# RFM95_LoRa_Shieldv0_2.net
KiCad netlist of a schematic drawn in EAGLE
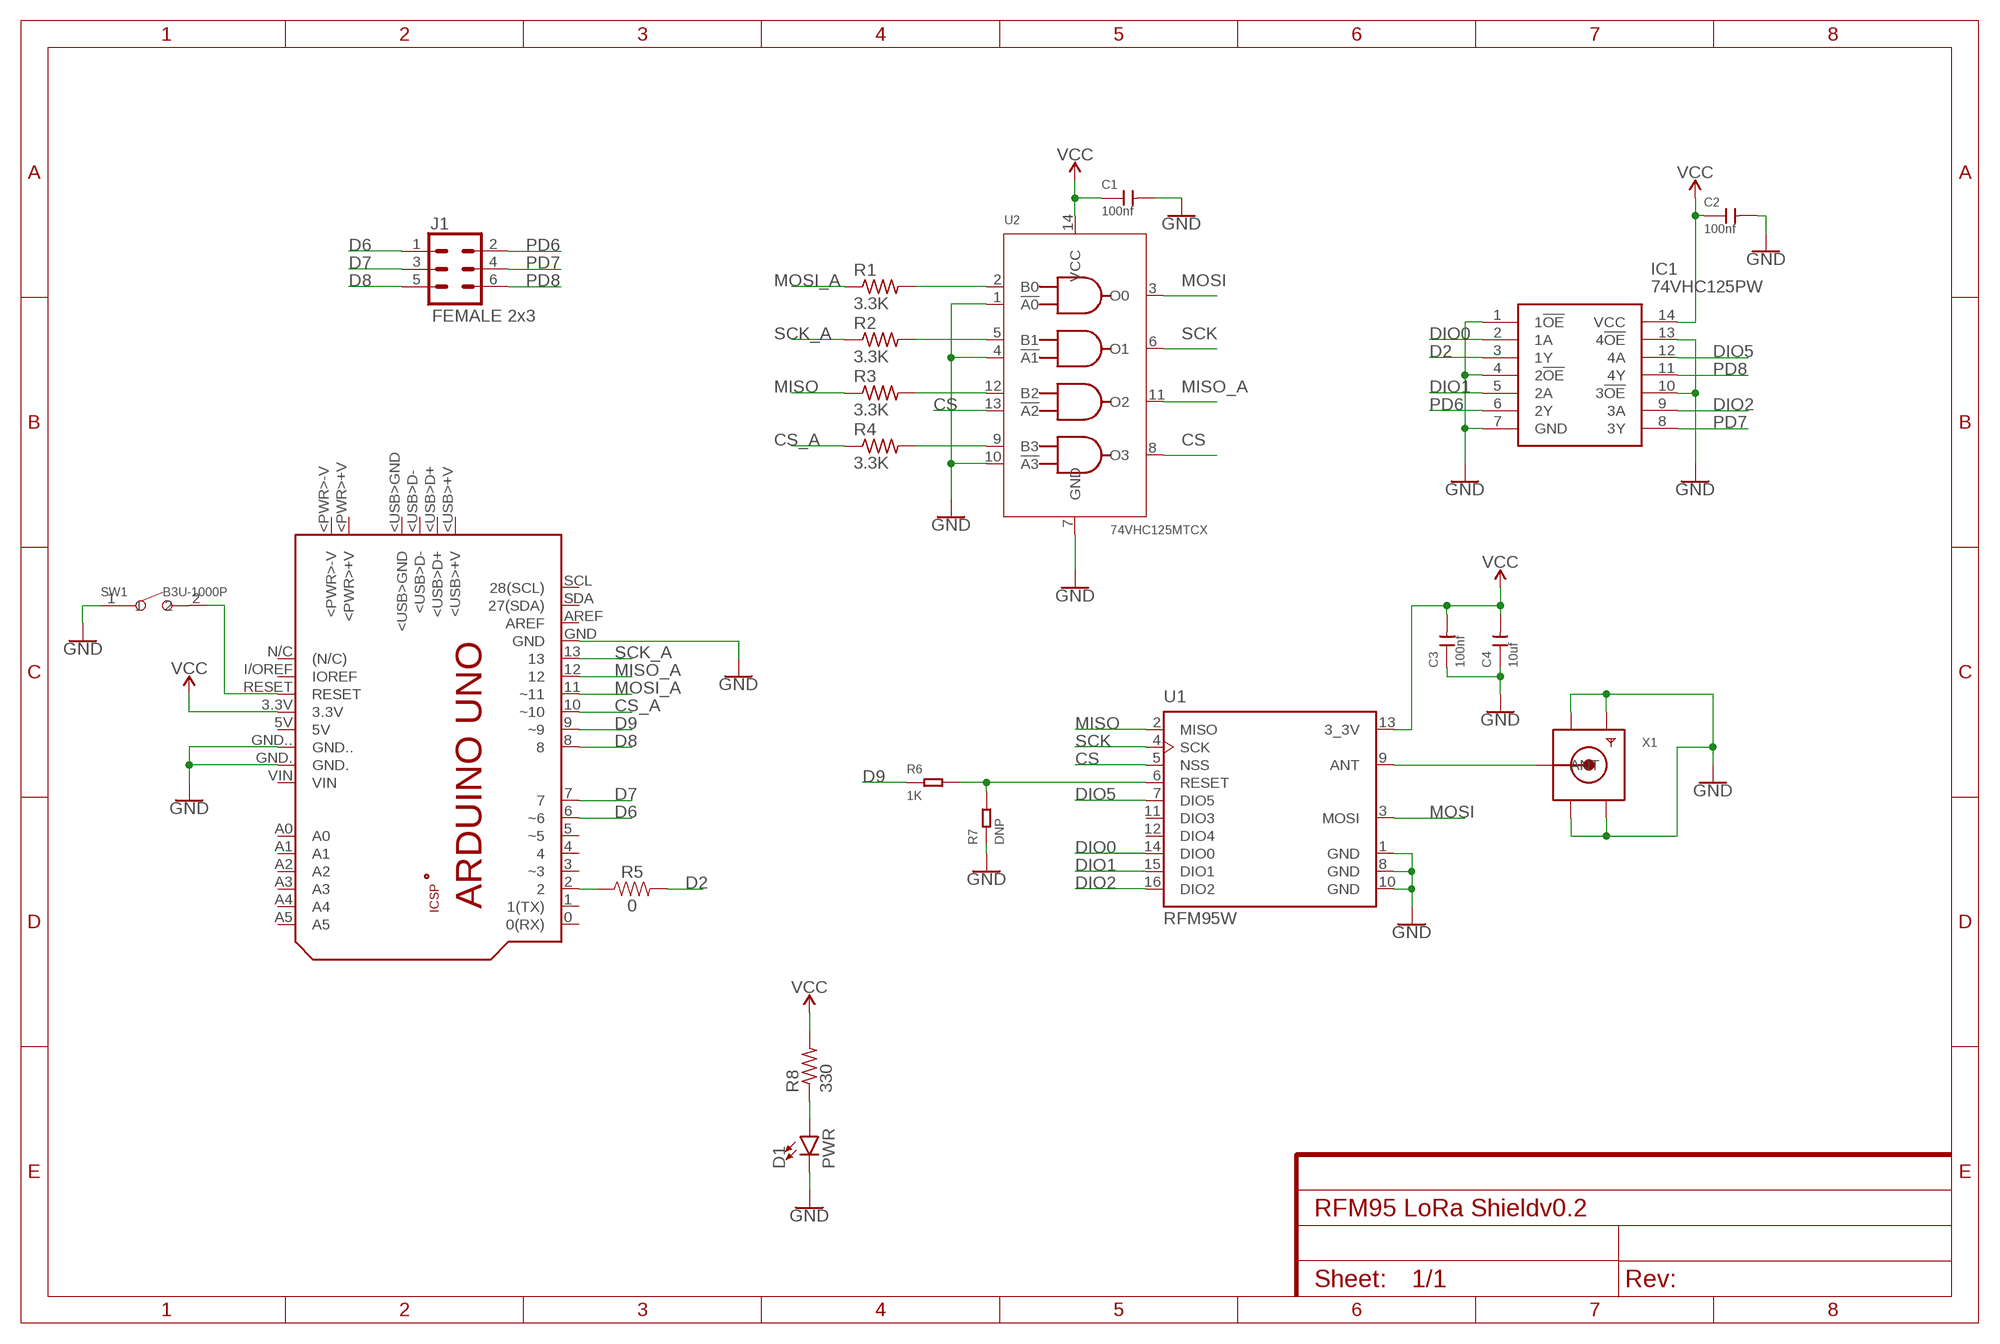
[diagram p0: schematic, sheet 1]

(export (version "E")
  (design (tool "Eeschema 10.0.6"))
  (components
    (comp (ref "C1")
      (value "100nf")
      (footprint "eagle-import:C0805")
      (fields (field (name "MPN") "CC0805KRX7R9BB104"))
      (libsource (lib "eagle-import") (part "CERAMIC-100NF-50V-10%-X7R(0805)"))
    )
    (comp (ref "C2")
      (value "100nf")
      (footprint "eagle-import:C0805")
      (fields (field (name "MPN") "CC0805KRX7R9BB104"))
      (libsource (lib "eagle-import") (part "CERAMIC-100NF-50V-10%-X7R(0805)"))
    )
    (comp (ref "C3")
      (value "100nf")
      (footprint "eagle-import:C0805")
      (fields (field (name "MPN") "CC0805KRX7R9BB104"))
      (libsource (lib "eagle-import") (part "CERAMIC-100NF-50V-10%-X7R(0805)"))
    )
    (comp (ref "C4")
      (value "10uf")
      (footprint "eagle-import:C0805")
      (fields (field (name "MPN") "CC0805KKX5R8BB106"))
      (libsource (lib "eagle-import") (part "CERAMIC-10UF-25V-10%-X5R(0805)"))
    )
    (comp (ref "D1")
      (value "PWR")
      (footprint "eagle-import:LED-1206")
      (libsource (lib "eagle-import") (part "LED-GREEN1206"))
    )
    (comp (ref "IC1")
      (value "74VHC125PW")
      (footprint "eagle-import:SOP65P640X110-14N")
      (fields (field (name "MANUFACTURER_PART_NUMBER") "74VHC125PW,118"))
      (libsource (lib "eagle-import") (part "74VHC125PW,118"))
    )
    (comp (ref "J1")
      (value "FEMALE 2x3")
      (footprint "eagle-import:2X3")
      (libsource (lib "eagle-import") (part "CONN_03X2FEMALE"))
    )
    (comp (ref "PCB1")
      (value "Arduino Uno")
      (footprint "eagle-import:ARDUINO_UNO")
      (libsource (lib "eagle-import") (part "ARDUINO_UNO"))
    )
    (comp (ref "R1")
      (value "3.3K")
      (footprint "eagle-import:M0805")
      (libsource (lib "eagle-import") (part "R-US_M0805"))
    )
    (comp (ref "R2")
      (value "3.3K")
      (footprint "eagle-import:M0805")
      (libsource (lib "eagle-import") (part "R-US_M0805"))
    )
    (comp (ref "R3")
      (value "3.3K")
      (footprint "eagle-import:M0805")
      (libsource (lib "eagle-import") (part "R-US_M0805"))
    )
    (comp (ref "R4")
      (value "3.3K")
      (footprint "eagle-import:M0805")
      (libsource (lib "eagle-import") (part "R-US_M0805"))
    )
    (comp (ref "R5")
      (value "0")
      (footprint "eagle-import:0603")
      (libsource (lib "eagle-import") (part "0OHM-0603-1/10W-5%"))
    )
    (comp (ref "R6")
      (value "1K")
      (footprint "eagle-import:R0805")
      (fields (field (name "MPN") "RC0805JR-071KL"))
      (libsource (lib "eagle-import") (part "SMD-RES-1K-5%-1/8W(0805)"))
    )
    (comp (ref "R7")
      (value "DNP")
      (footprint "eagle-import:R0805")
      (fields (field (name "MPN") "RC0805JR-071KL"))
      (libsource (lib "eagle-import") (part "SMD-RES-1K-5%-1/8W(0805)"))
    )
    (comp (ref "R8")
      (value "330")
      (footprint "eagle-import:M0805")
      (libsource (lib "eagle-import") (part "R-US_M0805"))
    )
    (comp (ref "SW1")
      (value "B3U-1000P")
      (footprint "eagle-import:SW2-2.6-3.0X2.5X1.2+0.4MM")
      (fields (field (name "MPN") "B3U-1000P-2P-SMD"))
      (libsource (lib "eagle-import") (part "SMD-BUTTON(2P-3.0X2.5X1.2+0.4MM)-B3U-1000P-2P-SMD"))
    )
    (comp (ref "U1")
      (value "RFM95W")
      (footprint "eagle-import:XCVR_RFM95W-868S2")
      (fields (field (name "MF") "RF") (field (name "MP") "RFM95W-868S2"))
      (libsource (lib "eagle-import") (part "RFM95W-868S2"))
    )
    (comp (ref "U2")
      (value "74VHC125MTCX")
      (footprint "eagle-import:TSSOP14-0.65-5X4.4MM")
      (libsource (lib "eagle-import") (part "LOGIC-74VHC125MTCX(TSSOP14)"))
    )
    (comp (ref "X1")
      (value "SMACONNECTOR")
      (footprint "eagle-import:SMA90_DIP")
      (libsource (lib "eagle-import") (part "SMACONNECTOR"))
    )
  )
  (nets
    (net (code "1") (name "/CS") (class "Default")
      (node (ref "U1") (pin "5") (pinfunction "NSS_5") (pintype "input"))
      (node (ref "U2") (pin "13") (pinfunction "~{A2}_13") (pintype "input"))
      (node (ref "U2") (pin "8") (pinfunction "O3_8") (pintype "bidirectional"))
    )
    (net (code "2") (name "/CS_A") (class "Default")
      (node (ref "PCB1") (pin "10") (pinfunction "~{10}_10") (pintype "bidirectional"))
      (node (ref "R4") (pin "1") (pinfunction "1_1") (pintype "passive"))
    )
    (net (code "3") (name "/D2") (class "Default")
      (node (ref "IC1") (pin "3") (pinfunction "1Y_3") (pintype "bidirectional"))
      (node (ref "R5") (pin "2") (pinfunction "2_2") (pintype "passive"))
    )
    (net (code "4") (name "/D6") (class "Default")
      (node (ref "J1") (pin "1") (pinfunction "1_1") (pintype "bidirectional"))
      (node (ref "PCB1") (pin "6") (pinfunction "~{6}_6") (pintype "bidirectional"))
    )
    (net (code "5") (name "/D7") (class "Default")
      (node (ref "J1") (pin "3") (pinfunction "3_3") (pintype "bidirectional"))
      (node (ref "PCB1") (pin "7") (pinfunction "7_7") (pintype "bidirectional"))
    )
    (net (code "6") (name "/D8") (class "Default")
      (node (ref "J1") (pin "5") (pinfunction "5_5") (pintype "bidirectional"))
      (node (ref "PCB1") (pin "8") (pinfunction "8_8") (pintype "bidirectional"))
    )
    (net (code "7") (name "/D9") (class "Default")
      (node (ref "PCB1") (pin "9") (pinfunction "~{9}_9") (pintype "bidirectional"))
      (node (ref "R6") (pin "1") (pinfunction "1_1") (pintype "passive"))
    )
    (net (code "8") (name "/DIO0") (class "Default")
      (node (ref "IC1") (pin "2") (pinfunction "1A_2") (pintype "bidirectional"))
      (node (ref "U1") (pin "14") (pinfunction "DIO0_14") (pintype "bidirectional"))
    )
    (net (code "9") (name "/DIO1") (class "Default")
      (node (ref "IC1") (pin "5") (pinfunction "2A_5") (pintype "bidirectional"))
      (node (ref "U1") (pin "15") (pinfunction "DIO1_15") (pintype "bidirectional"))
    )
    (net (code "10") (name "/DIO2") (class "Default")
      (node (ref "IC1") (pin "9") (pinfunction "3A_9") (pintype "bidirectional"))
      (node (ref "U1") (pin "16") (pinfunction "DIO2_16") (pintype "bidirectional"))
    )
    (net (code "11") (name "/DIO5") (class "Default")
      (node (ref "IC1") (pin "12") (pinfunction "4A_12") (pintype "bidirectional"))
      (node (ref "U1") (pin "7") (pinfunction "DIO5_7") (pintype "bidirectional"))
    )
    (net (code "12") (name "/MISO") (class "Default")
      (node (ref "R3") (pin "1") (pinfunction "1_1") (pintype "passive"))
      (node (ref "U1") (pin "2") (pinfunction "MISO_2") (pintype "input"))
    )
    (net (code "13") (name "/MISO_A") (class "Default")
      (node (ref "PCB1") (pin "12") (pinfunction "12_12") (pintype "bidirectional"))
      (node (ref "U2") (pin "11") (pinfunction "O2_11") (pintype "bidirectional"))
    )
    (net (code "14") (name "/MOSI") (class "Default")
      (node (ref "U1") (pin "3") (pinfunction "MOSI_3") (pintype "output"))
      (node (ref "U2") (pin "3") (pinfunction "O0_3") (pintype "bidirectional"))
    )
    (net (code "15") (name "/MOSI_A") (class "Default")
      (node (ref "PCB1") (pin "11") (pinfunction "~{11}_11") (pintype "bidirectional"))
      (node (ref "R1") (pin "1") (pinfunction "1_1") (pintype "passive"))
    )
    (net (code "16") (name "/PD6") (class "Default")
      (node (ref "IC1") (pin "6") (pinfunction "2Y_6") (pintype "bidirectional"))
      (node (ref "J1") (pin "2") (pinfunction "2_2") (pintype "bidirectional"))
    )
    (net (code "17") (name "/PD7") (class "Default")
      (node (ref "IC1") (pin "8") (pinfunction "3Y_8") (pintype "bidirectional"))
      (node (ref "J1") (pin "4") (pinfunction "4_4") (pintype "bidirectional"))
    )
    (net (code "18") (name "/PD8") (class "Default")
      (node (ref "IC1") (pin "11") (pinfunction "4Y_11") (pintype "bidirectional"))
      (node (ref "J1") (pin "6") (pinfunction "6_6") (pintype "bidirectional"))
    )
    (net (code "19") (name "/SCK") (class "Default")
      (node (ref "U1") (pin "4") (pinfunction "SCK_4") (pintype "input"))
      (node (ref "U2") (pin "6") (pinfunction "O1_6") (pintype "bidirectional"))
    )
    (net (code "20") (name "/SCK_A") (class "Default")
      (node (ref "PCB1") (pin "13") (pinfunction "13_13") (pintype "bidirectional"))
      (node (ref "R2") (pin "1") (pinfunction "1_1") (pintype "passive"))
    )
    (net (code "21") (name "GND") (class "Default")
      (node (ref "C1") (pin "2") (pinfunction "2_2") (pintype "passive"))
      (node (ref "C2") (pin "2") (pinfunction "2_2") (pintype "passive"))
      (node (ref "C3") (pin "1") (pinfunction "1_1") (pintype "passive"))
      (node (ref "C4") (pin "1") (pinfunction "1_1") (pintype "passive"))
      (node (ref "D1") (pin "C") (pinfunction "C_C") (pintype "passive"))
      (node (ref "IC1") (pin "1") (pinfunction "1~{OE}_1") (pintype "bidirectional"))
      (node (ref "IC1") (pin "10") (pinfunction "3~{OE}_10") (pintype "bidirectional"))
      (node (ref "IC1") (pin "13") (pinfunction "4~{OE}_13") (pintype "bidirectional"))
      (node (ref "IC1") (pin "4") (pinfunction "2~{OE}_4") (pintype "bidirectional"))
      (node (ref "IC1") (pin "7") (pinfunction "GND_7") (pintype "bidirectional"))
      (node (ref "PCB1") (pin "GND") (pinfunction "GND_GND") (pintype "bidirectional"))
      (node (ref "PCB1") (pin "GND.") (pinfunction "GND._GND.") (pintype "bidirectional"))
      (node (ref "PCB1") (pin "GND..") (pinfunction "GND.._GND..") (pintype "bidirectional"))
      (node (ref "R7") (pin "1") (pinfunction "1_1") (pintype "passive"))
      (node (ref "SW1") (pin "1") (pinfunction "1_1") (pintype "bidirectional"))
      (node (ref "U1") (pin "1") (pinfunction "GND_1") (pintype "power_in"))
      (node (ref "U1") (pin "10") (pinfunction "GND_10") (pintype "power_in"))
      (node (ref "U1") (pin "8") (pinfunction "GND_8") (pintype "power_in"))
      (node (ref "U2") (pin "1") (pinfunction "~{A0}_1") (pintype "power_in"))
      (node (ref "U2") (pin "10") (pinfunction "~{A3}_10") (pintype "bidirectional"))
      (node (ref "U2") (pin "4") (pinfunction "~{A1}_4") (pintype "power_in"))
      (node (ref "U2") (pin "7") (pinfunction "GND_7") (pintype "power_in"))
      (node (ref "X1") (pin "GND1") (pinfunction "GND1_GND1") (pintype "power_in"))
      (node (ref "X1") (pin "GND2") (pinfunction "GND2_GND2") (pintype "power_in"))
      (node (ref "X1") (pin "GND3") (pinfunction "GND3_GND3") (pintype "power_in"))
      (node (ref "X1") (pin "GND4") (pinfunction "GND4_GND4") (pintype "power_in"))
    )
    (net (code "22") (name "Net-(D1-PadA)") (class "Default")
      (node (ref "D1") (pin "A") (pinfunction "A_A") (pintype "passive"))
      (node (ref "R8") (pin "1") (pinfunction "1_1") (pintype "passive"))
    )
    (net (code "23") (name "Net-(PCB1-Pad2)") (class "Default")
      (node (ref "PCB1") (pin "2") (pinfunction "2_2") (pintype "bidirectional"))
      (node (ref "R5") (pin "1") (pinfunction "1_1") (pintype "passive"))
    )
    (net (code "24") (name "Net-(PCB1-PadRESET)") (class "Default")
      (node (ref "PCB1") (pin "RESET") (pinfunction "RESET_RESET") (pintype "bidirectional"))
      (node (ref "SW1") (pin "2") (pinfunction "2_2") (pintype "bidirectional"))
    )
    (net (code "25") (name "Net-(U1-ANT)") (class "Default")
      (node (ref "U1") (pin "9") (pinfunction "ANT_9") (pintype "passive"))
      (node (ref "X1") (pin "ANTENNA") (pinfunction "ANT_ANTENNA") (pintype "bidirectional"))
    )
    (net (code "26") (name "Net-(U1-RESET)") (class "Default")
      (node (ref "R6") (pin "2") (pinfunction "2_2") (pintype "passive"))
      (node (ref "R7") (pin "2") (pinfunction "2_2") (pintype "passive"))
      (node (ref "U1") (pin "6") (pinfunction "RESET_6") (pintype "bidirectional"))
    )
    (net (code "27") (name "Net-(U2-B0)") (class "Default")
      (node (ref "R1") (pin "2") (pinfunction "2_2") (pintype "passive"))
      (node (ref "U2") (pin "2") (pinfunction "B0_2") (pintype "bidirectional"))
    )
    (net (code "28") (name "Net-(U2-B1)") (class "Default")
      (node (ref "R2") (pin "2") (pinfunction "2_2") (pintype "passive"))
      (node (ref "U2") (pin "5") (pinfunction "B1_5") (pintype "bidirectional"))
    )
    (net (code "29") (name "Net-(U2-B2)") (class "Default")
      (node (ref "R3") (pin "2") (pinfunction "2_2") (pintype "passive"))
      (node (ref "U2") (pin "12") (pinfunction "B2_12") (pintype "bidirectional"))
    )
    (net (code "30") (name "Net-(U2-B3)") (class "Default")
      (node (ref "R4") (pin "2") (pinfunction "2_2") (pintype "passive"))
      (node (ref "U2") (pin "9") (pinfunction "B3_9") (pintype "bidirectional"))
    )
    (net (code "31") (name "VCC") (class "Default")
      (node (ref "C1") (pin "1") (pinfunction "1_1") (pintype "passive"))
      (node (ref "C2") (pin "1") (pinfunction "1_1") (pintype "passive"))
      (node (ref "C3") (pin "2") (pinfunction "2_2") (pintype "passive"))
      (node (ref "C4") (pin "2") (pinfunction "2_2") (pintype "passive"))
      (node (ref "IC1") (pin "14") (pinfunction "VCC_14") (pintype "bidirectional"))
      (node (ref "PCB1") (pin "3.3V") (pinfunction "3.3V_3.3V") (pintype "bidirectional"))
      (node (ref "R8") (pin "2") (pinfunction "2_2") (pintype "passive"))
      (node (ref "U1") (pin "13") (pinfunction "3_3V_13") (pintype "power_in"))
      (node (ref "U2") (pin "14") (pinfunction "VCC_14") (pintype "power_in"))
    )
    (net (code "32") (name "unconnected-(PCB1-(N{slash}C)-PadN{slash}C)") (class "Default")
      (node (ref "PCB1") (pin "N/C") (pinfunction "(N/C)_N/C") (pintype "bidirectional"))
    )
    (net (code "33") (name "unconnected-(PCB1-0(RX)-Pad0)") (class "Default")
      (node (ref "PCB1") (pin "0") (pinfunction "0(RX)_0") (pintype "bidirectional"))
    )
    (net (code "34") (name "unconnected-(PCB1-1(TX)-Pad1)") (class "Default")
      (node (ref "PCB1") (pin "1") (pinfunction "1(TX)_1") (pintype "bidirectional"))
    )
    (net (code "35") (name "unconnected-(PCB1-27(SDA)-PadSDA)") (class "Default")
      (node (ref "PCB1") (pin "SDA") (pinfunction "27(SDA)_SDA") (pintype "bidirectional"))
    )
    (net (code "36") (name "unconnected-(PCB1-28(SCL)-PadSCL)") (class "Default")
      (node (ref "PCB1") (pin "SCL") (pinfunction "28(SCL)_SCL") (pintype "bidirectional"))
    )
    (net (code "37") (name "unconnected-(PCB1-IOREF-PadI{slash}OREF)") (class "Default")
      (node (ref "PCB1") (pin "I/OREF") (pinfunction "IOREF_I/OREF") (pintype "bidirectional"))
    )
    (net (code "38") (name "unconnected-(PCB1-Pad+5V)") (class "Default")
      (node (ref "PCB1") (pin "+5V") (pinfunction "+5V_+5V") (pintype "bidirectional"))
    )
    (net (code "39") (name "unconnected-(PCB1-Pad4)") (class "Default")
      (node (ref "PCB1") (pin "4") (pinfunction "4_4") (pintype "bidirectional"))
    )
    (net (code "40") (name "unconnected-(PCB1-Pad5V)") (class "Default")
      (node (ref "PCB1") (pin "5V") (pinfunction "5V_5V") (pintype "bidirectional"))
    )
    (net (code "41") (name "unconnected-(PCB1-Pad<PWR>+V)") (class "Default")
      (node (ref "PCB1") (pin "<PWR>+V") (pinfunction "<PWR>+V_<PWR>+V") (pintype "bidirectional"))
    )
    (net (code "42") (name "unconnected-(PCB1-Pad<PWR>-V)") (class "Default")
      (node (ref "PCB1") (pin "<PWR>-V") (pinfunction "<PWR>-V_<PWR>-V") (pintype "bidirectional"))
    )
    (net (code "43") (name "unconnected-(PCB1-Pad<USB>+V)") (class "Default")
      (node (ref "PCB1") (pin "<USB>+V") (pinfunction "<USB>+V_<USB>+V") (pintype "bidirectional"))
    )
    (net (code "44") (name "unconnected-(PCB1-Pad<USB>D+)") (class "Default")
      (node (ref "PCB1") (pin "<USB>D+") (pinfunction "<USB>D+_<USB>D+") (pintype "bidirectional"))
    )
    (net (code "45") (name "unconnected-(PCB1-Pad<USB>D-)") (class "Default")
      (node (ref "PCB1") (pin "<USB>D-") (pinfunction "<USB>D-_<USB>D-") (pintype "bidirectional"))
    )
    (net (code "46") (name "unconnected-(PCB1-Pad<USB>GND)") (class "Default")
      (node (ref "PCB1") (pin "<USB>GND") (pinfunction "<USB>GND_<USB>GND") (pintype "bidirectional"))
    )
    (net (code "47") (name "unconnected-(PCB1-PadA0)") (class "Default")
      (node (ref "PCB1") (pin "A0") (pinfunction "A0_A0") (pintype "bidirectional"))
    )
    (net (code "48") (name "unconnected-(PCB1-PadA1)") (class "Default")
      (node (ref "PCB1") (pin "A1") (pinfunction "A1_A1") (pintype "bidirectional"))
    )
    (net (code "49") (name "unconnected-(PCB1-PadA2)") (class "Default")
      (node (ref "PCB1") (pin "A2") (pinfunction "A2_A2") (pintype "bidirectional"))
    )
    (net (code "50") (name "unconnected-(PCB1-PadA3)") (class "Default")
      (node (ref "PCB1") (pin "A3") (pinfunction "A3_A3") (pintype "bidirectional"))
    )
    (net (code "51") (name "unconnected-(PCB1-PadA4)") (class "Default")
      (node (ref "PCB1") (pin "A4") (pinfunction "A4_A4") (pintype "bidirectional"))
    )
    (net (code "52") (name "unconnected-(PCB1-PadA5)") (class "Default")
      (node (ref "PCB1") (pin "A5") (pinfunction "A5_A5") (pintype "bidirectional"))
    )
    (net (code "53") (name "unconnected-(PCB1-PadAREF)") (class "Default")
      (node (ref "PCB1") (pin "AREF") (pinfunction "AREF_AREF") (pintype "bidirectional"))
    )
    (net (code "54") (name "unconnected-(PCB1-PadGND_)") (class "Default")
      (node (ref "PCB1") (pin "GND_") (pinfunction "GND__GND_") (pintype "bidirectional"))
    )
    (net (code "55") (name "unconnected-(PCB1-PadMISO)") (class "Default")
      (node (ref "PCB1") (pin "MISO") (pinfunction "MISO_MISO") (pintype "bidirectional"))
    )
    (net (code "56") (name "unconnected-(PCB1-PadMOSI)") (class "Default")
      (node (ref "PCB1") (pin "MOSI") (pinfunction "MOSI_MOSI") (pintype "bidirectional"))
    )
    (net (code "57") (name "unconnected-(PCB1-PadRESET.)") (class "Default")
      (node (ref "PCB1") (pin "RESET.") (pinfunction "RESET._RESET.") (pintype "bidirectional"))
    )
    (net (code "58") (name "unconnected-(PCB1-PadSCK)") (class "Default")
      (node (ref "PCB1") (pin "SCK") (pinfunction "SCK_SCK") (pintype "bidirectional"))
    )
    (net (code "59") (name "unconnected-(PCB1-PadVIN)") (class "Default")
      (node (ref "PCB1") (pin "VIN") (pinfunction "VIN_VIN") (pintype "bidirectional"))
    )
    (net (code "60") (name "unconnected-(PCB1-~{3}-Pad3)") (class "Default")
      (node (ref "PCB1") (pin "3") (pinfunction "~{3}_3") (pintype "bidirectional"))
    )
    (net (code "61") (name "unconnected-(PCB1-~{5}-Pad5)") (class "Default")
      (node (ref "PCB1") (pin "5") (pinfunction "~{5}_5") (pintype "bidirectional"))
    )
    (net (code "62") (name "unconnected-(U1-DIO3-Pad11)") (class "Default")
      (node (ref "U1") (pin "11") (pinfunction "DIO3_11") (pintype "bidirectional"))
    )
    (net (code "63") (name "unconnected-(U1-DIO4-Pad12)") (class "Default")
      (node (ref "U1") (pin "12") (pinfunction "DIO4_12") (pintype "bidirectional"))
    )
  )
)
